# TS5A23167DCUR_breakout.net
KiCad netlist of a schematic drawn in EAGLE
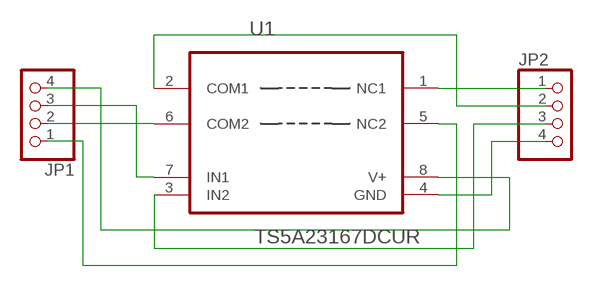
[diagram p0: schematic, sheet 1]

(export (version "E")
  (design (tool "Eeschema 10.0.6"))
  (components
    (comp (ref "JP1")
      (value "PINHD-1X4")
      (footprint "eagle-import:1X04")
      (libsource (lib "eagle-import") (part "PINHD-1X4"))
    )
    (comp (ref "JP2")
      (value "PINHD-1X4")
      (footprint "eagle-import:1X04")
      (libsource (lib "eagle-import") (part "PINHD-1X4"))
    )
    (comp (ref "U1")
      (value "TS5A23167DCUR")
      (footprint "eagle-import:SOP50P310X90-8N")
      (fields (field (name "MF") "Texas Instruments"))
      (libsource (lib "eagle-import") (part "TS5A23167DCUR"))
    )
  )
  (nets
    (net (code "1") (name "Net-(U1-COM1)") (class "Default")
      (node (ref "JP2") (pin "2") (pinfunction "2_2") (pintype "passive"))
      (node (ref "U1") (pin "2") (pinfunction "COM1_2") (pintype "bidirectional"))
    )
    (net (code "2") (name "Net-(U1-COM2)") (class "Default")
      (node (ref "JP1") (pin "2") (pinfunction "2_2") (pintype "passive"))
      (node (ref "U1") (pin "6") (pinfunction "COM2_6") (pintype "bidirectional"))
    )
    (net (code "3") (name "Net-(U1-GND)") (class "Default")
      (node (ref "JP2") (pin "4") (pinfunction "4_4") (pintype "passive"))
      (node (ref "U1") (pin "4") (pinfunction "GND_4") (pintype "passive"))
    )
    (net (code "4") (name "Net-(U1-IN1)") (class "Default")
      (node (ref "JP1") (pin "3") (pinfunction "3_3") (pintype "passive"))
      (node (ref "U1") (pin "7") (pinfunction "IN1_7") (pintype "input"))
    )
    (net (code "5") (name "Net-(U1-IN2)") (class "Default")
      (node (ref "JP2") (pin "3") (pinfunction "3_3") (pintype "passive"))
      (node (ref "U1") (pin "3") (pinfunction "IN2_3") (pintype "input"))
    )
    (net (code "6") (name "Net-(U1-NC1)") (class "Default")
      (node (ref "JP2") (pin "1") (pinfunction "1_1") (pintype "passive"))
      (node (ref "U1") (pin "1") (pinfunction "NC1_1") (pintype "bidirectional"))
    )
    (net (code "7") (name "Net-(U1-NC2)") (class "Default")
      (node (ref "JP1") (pin "1") (pinfunction "1_1") (pintype "passive"))
      (node (ref "U1") (pin "5") (pinfunction "NC2_5") (pintype "bidirectional"))
    )
    (net (code "8") (name "Net-(U1-V+)") (class "Default")
      (node (ref "JP1") (pin "4") (pinfunction "4_4") (pintype "passive"))
      (node (ref "U1") (pin "8") (pinfunction "V+_8") (pintype "power_in"))
    )
  )
)
